# mp3player_v7_Laderegler_LTC4063_4050.net
KiCad netlist of a schematic drawn in EAGLE
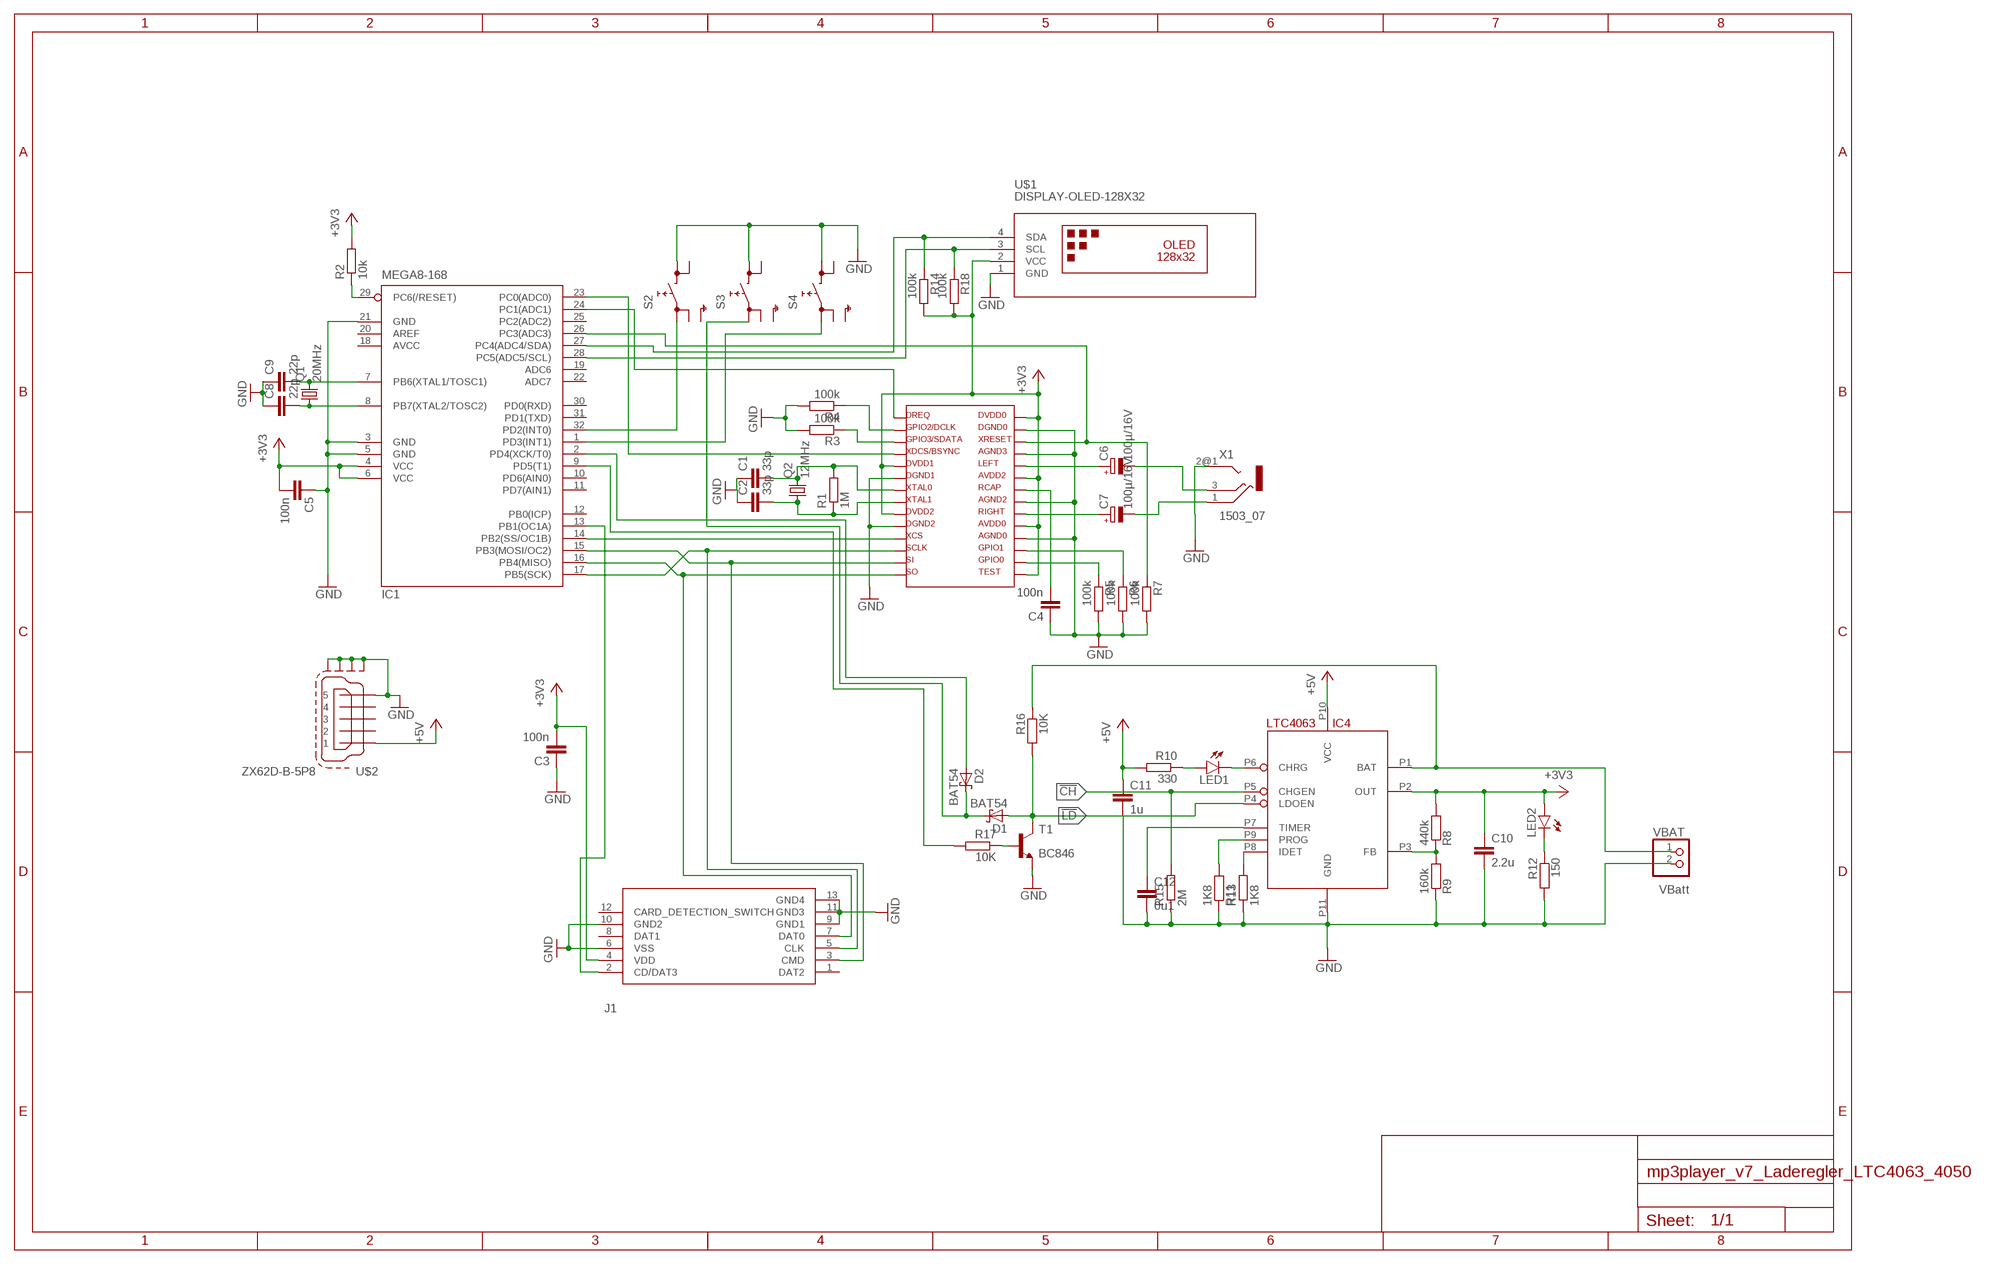
[diagram p0: schematic, sheet 1]

(export (version "E")
  (design (tool "Eeschema 10.0.6"))
  (components
    (comp (ref "C1")
      (value "33p")
      (footprint "eagle-import:C1206K")
      (libsource (lib "eagle-import") (part "C-EUC1206K"))
    )
    (comp (ref "C2")
      (value "33p")
      (footprint "eagle-import:C1206K")
      (libsource (lib "eagle-import") (part "C-EUC1206K"))
    )
    (comp (ref "C3")
      (value "100n")
      (footprint "eagle-import:C1206K")
      (libsource (lib "eagle-import") (part "C-EUC1206K"))
    )
    (comp (ref "C4")
      (value "100n")
      (footprint "eagle-import:C1206K")
      (libsource (lib "eagle-import") (part "C-EUC1206K"))
    )
    (comp (ref "C5")
      (value "100n")
      (footprint "eagle-import:C1206K")
      (libsource (lib "eagle-import") (part "C-EUC1206K"))
    )
    (comp (ref "C6")
      (value "100µ/16V")
      (footprint "eagle-import:UD-6,3X7,7_NICHICON")
      (libsource (lib "eagle-import") (part "CPOL-EUUD-6,3X7,7"))
    )
    (comp (ref "C7")
      (value "100µ/16V")
      (footprint "eagle-import:UD-6,3X7,7_NICHICON")
      (libsource (lib "eagle-import") (part "CPOL-EUUD-6,3X7,7"))
    )
    (comp (ref "C8")
      (value "22p")
      (footprint "eagle-import:C1206K")
      (libsource (lib "eagle-import") (part "rcl_334_C-EUC1206K"))
    )
    (comp (ref "C9")
      (value "22p")
      (footprint "eagle-import:C1206K")
      (libsource (lib "eagle-import") (part "rcl_334_C-EUC1206K"))
    )
    (comp (ref "C10")
      (value "2.2u")
      (footprint "eagle-import:C0805K")
      (libsource (lib "eagle-import") (part "C-EUC0805K"))
    )
    (comp (ref "C11")
      (value "1u")
      (footprint "eagle-import:C0805K")
      (libsource (lib "eagle-import") (part "C-EUC0805K"))
    )
    (comp (ref "C12")
      (value "0u1")
      (footprint "eagle-import:C0805K")
      (libsource (lib "eagle-import") (part "C-EUC0805K"))
    )
    (comp (ref "D1")
      (value "BAT54")
      (footprint "eagle-import:SOT23")
      (libsource (lib "eagle-import") (part "BAT54"))
    )
    (comp (ref "D2")
      (value "BAT54")
      (footprint "eagle-import:SOT23")
      (libsource (lib "eagle-import") (part "BAT54"))
    )
    (comp (ref "IC1")
      (value "MEGA8-168")
      (footprint "eagle-import:TQFP32-08")
      (fields (field (name "MPN") "ATMEGA8-16AU"))
      (libsource (lib "eagle-import") (part "MEGA8-AI"))
    )
    (comp (ref "IC2")
      (value "VS1011")
      (footprint "eagle-import:SOIC-28")
      (libsource (lib "eagle-import") (part "VS1011"))
    )
    (comp (ref "IC4")
      (value "LTC4063")
      (footprint "eagle-import:LTC4063")
      (libsource (lib "eagle-import") (part "LTC4063"))
    )
    (comp (ref "J1")
      (value "DM3CS-SF")
      (footprint "eagle-import:DM3CS-SF")
      (fields (field (name "RS_PART_NUMBER") "1664833"))
      (libsource (lib "eagle-import") (part "DM3CS-SF"))
    )
    (comp (ref "LED1")
      (value "LG_T679-E1F1-1")
      (footprint "eagle-import:PLCC2")
      (libsource (lib "eagle-import") (part "_T679-?-1E1F1LG"))
    )
    (comp (ref "LED2")
      (value "LG_T679-E1F1-1")
      (footprint "eagle-import:PLCC2")
      (libsource (lib "eagle-import") (part "_T679-?-1E1F1LG"))
    )
    (comp (ref "Q1")
      (value "20MHz")
      (footprint "eagle-import:HC49UP")
      (libsource (lib "eagle-import") (part "crystal_204_CRYSTALHC49UP"))
    )
    (comp (ref "Q2")
      (value "12MHz")
      (footprint "eagle-import:HC49UP")
      (libsource (lib "eagle-import") (part "CRYSTALHC49UP"))
    )
    (comp (ref "R1")
      (value "1M")
      (footprint "eagle-import:R0805")
      (libsource (lib "eagle-import") (part "rcl_334_R-EU_R0805"))
    )
    (comp (ref "R2")
      (value "10k")
      (footprint "eagle-import:0207_7")
      (libsource (lib "eagle-import") (part "rcl_334_R-EU_0207/7"))
    )
    (comp (ref "R3")
      (value "100k")
      (footprint "eagle-import:R0805")
      (libsource (lib "eagle-import") (part "rcl_334_R-EU_R0805"))
    )
    (comp (ref "R4")
      (value "100k")
      (footprint "eagle-import:R0805")
      (libsource (lib "eagle-import") (part "rcl_334_R-EU_R0805"))
    )
    (comp (ref "R5")
      (value "100k")
      (footprint "eagle-import:R0805")
      (libsource (lib "eagle-import") (part "rcl_334_R-EU_R0805"))
    )
    (comp (ref "R6")
      (value "100k")
      (footprint "eagle-import:R0805")
      (libsource (lib "eagle-import") (part "rcl_334_R-EU_R0805"))
    )
    (comp (ref "R7")
      (value "100k")
      (footprint "eagle-import:0207_15")
      (libsource (lib "eagle-import") (part "rcl_334_R-EU_0207/15"))
    )
    (comp (ref "R8")
      (value "440k")
      (footprint "eagle-import:R0805")
      (libsource (lib "eagle-import") (part "rcl_334_R-EU_R0805"))
    )
    (comp (ref "R9")
      (value "160k")
      (footprint "eagle-import:R0805")
      (libsource (lib "eagle-import") (part "rcl_334_R-EU_R0805"))
    )
    (comp (ref "R10")
      (value "330")
      (footprint "eagle-import:R0805")
      (libsource (lib "eagle-import") (part "rcl_334_R-EU_R0805"))
    )
    (comp (ref "R11")
      (value "1K8")
      (footprint "eagle-import:R0805")
      (libsource (lib "eagle-import") (part "R-EU_R0805"))
    )
    (comp (ref "R12")
      (value "150")
      (footprint "eagle-import:R0805")
      (libsource (lib "eagle-import") (part "rcl_334_R-EU_R0805"))
    )
    (comp (ref "R13")
      (value "1K8")
      (footprint "eagle-import:R0805")
      (libsource (lib "eagle-import") (part "rcl_334_R-EU_R0805"))
    )
    (comp (ref "R14")
      (value "100k")
      (footprint "eagle-import:R0805")
      (libsource (lib "eagle-import") (part "rcl_334_R-EU_R0805"))
    )
    (comp (ref "R15")
      (value "2M")
      (footprint "eagle-import:R0805")
      (libsource (lib "eagle-import") (part "rcl_334_R-EU_R0805"))
    )
    (comp (ref "R16")
      (value "10K")
      (footprint "eagle-import:0207_7")
      (libsource (lib "eagle-import") (part "rcl_334_R-EU_0207/7"))
    )
    (comp (ref "R17")
      (value "10K")
      (footprint "eagle-import:R0805")
      (libsource (lib "eagle-import") (part "rcl_334_R-EU_R0805"))
    )
    (comp (ref "R18")
      (value "100k")
      (footprint "eagle-import:R0805")
      (libsource (lib "eagle-import") (part "rcl_334_R-EU_R0805"))
    )
    (comp (ref "S2")
      (value "SKHMPSE010")
      (footprint "eagle-import:SKHMPXE010")
      (libsource (lib "eagle-import") (part "SKHMPE010S"))
    )
    (comp (ref "S3")
      (value "SKHMPSE010")
      (footprint "eagle-import:SKHMPXE010")
      (libsource (lib "eagle-import") (part "SKHMPE010S"))
    )
    (comp (ref "S4")
      (value "SKHMPSE010")
      (footprint "eagle-import:SKHMPXE010")
      (libsource (lib "eagle-import") (part "SKHMPE010S"))
    )
    (comp (ref "T1")
      (value "BC846")
      (footprint "eagle-import:SOT23")
      (libsource (lib "eagle-import") (part "BC846"))
    )
    (comp (ref "U$1")
      (value "DISPLAY-OLED-128X32")
      (footprint "eagle-import:DISPLAY-OLED-128X32")
      (libsource (lib "eagle-import") (part "DISPLAY-OLED-128X32"))
    )
    (comp (ref "U$2")
      (value "ZX62D-B-5P8")
      (footprint "eagle-import:ZX62D-B-5P8")
      (libsource (lib "eagle-import") (part "ZX62D-B-5P8"))
    )
    (comp (ref "VBAT")
      (value "PINHD-1X2")
      (footprint "eagle-import:1X02")
      (libsource (lib "eagle-import") (part "PINHD-1X2"))
    )
    (comp (ref "X1")
      (value "1503_07")
      (footprint "eagle-import:1503_07")
      (libsource (lib "eagle-import") (part "1503_?07"))
    )
  )
  (nets
    (net (code "1") (name "+3V3") (class "Default")
      (node (ref "C10") (pin "1") (pinfunction "1_1") (pintype "passive"))
      (node (ref "C3") (pin "2") (pinfunction "2_2") (pintype "passive"))
      (node (ref "C5") (pin "2") (pinfunction "2_2") (pintype "passive"))
      (node (ref "IC1") (pin "4") (pinfunction "VCC_4") (pintype "power_in"))
      (node (ref "IC1") (pin "6") (pinfunction "VCC_6") (pintype "power_in"))
      (node (ref "IC2") (pin "15") (pinfunction "P$15_15") (pintype "bidirectional"))
      (node (ref "IC2") (pin "19") (pinfunction "P$19_19") (pintype "bidirectional"))
      (node (ref "IC2") (pin "23") (pinfunction "P$23_23") (pintype "bidirectional"))
      (node (ref "IC2") (pin "28") (pinfunction "P$28_28") (pintype "bidirectional"))
      (node (ref "IC2") (pin "5") (pinfunction "P$5_5") (pintype "bidirectional"))
      (node (ref "IC2") (pin "9") (pinfunction "P$9_9") (pintype "bidirectional"))
      (node (ref "IC4") (pin "P2") (pinfunction "OUT_P2") (pintype "output"))
      (node (ref "J1") (pin "4") (pinfunction "VDD_4") (pintype "bidirectional"))
      (node (ref "LED2") (pin "A") (pinfunction "A_A") (pintype "passive"))
      (node (ref "R14") (pin "2") (pinfunction "2_2") (pintype "passive"))
      (node (ref "R18") (pin "2") (pinfunction "2_2") (pintype "passive"))
      (node (ref "R2") (pin "2") (pinfunction "2_2") (pintype "passive"))
      (node (ref "R8") (pin "2") (pinfunction "2_2") (pintype "passive"))
      (node (ref "U$1") (pin "2") (pinfunction "VCC_2") (pintype "power_in"))
    )
    (net (code "2") (name "+5V") (class "Default")
      (node (ref "C11") (pin "1") (pinfunction "1_1") (pintype "passive"))
      (node (ref "IC4") (pin "P10") (pinfunction "VCC_P10") (pintype "power_in"))
      (node (ref "R10") (pin "2") (pinfunction "2_2") (pintype "passive"))
      (node (ref "U$2") (pin "P$1") (pinfunction "1_P$1") (pintype "passive"))
    )
    (net (code "3") (name "/AVCC") (class "Default")
      (node (ref "IC1") (pin "18") (pinfunction "AVCC_18") (pintype "power_in"))
    )
    (net (code "4") (name "/~{CH}") (class "Default")
      (node (ref "IC4") (pin "P5") (pinfunction "CHGEN_P5") (pintype "input"))
      (node (ref "R15") (pin "2") (pinfunction "2_2") (pintype "passive"))
    )
    (net (code "5") (name "/~{LD}") (class "Default")
      (node (ref "D1") (pin "1") (pinfunction "A_1") (pintype "passive"))
      (node (ref "IC4") (pin "P4") (pinfunction "LDOEN_P4") (pintype "input"))
      (node (ref "R16") (pin "2") (pinfunction "2_2") (pintype "passive"))
      (node (ref "T1") (pin "3") (pinfunction "C_3") (pintype "passive"))
    )
    (net (code "6") (name "GND") (class "Default")
      (node (ref "C1") (pin "1") (pinfunction "1_1") (pintype "passive"))
      (node (ref "C10") (pin "2") (pinfunction "2_2") (pintype "passive"))
      (node (ref "C11") (pin "2") (pinfunction "2_2") (pintype "passive"))
      (node (ref "C12") (pin "2") (pinfunction "2_2") (pintype "passive"))
      (node (ref "C2") (pin "1") (pinfunction "1_1") (pintype "passive"))
      (node (ref "C3") (pin "1") (pinfunction "1_1") (pintype "passive"))
      (node (ref "C4") (pin "1") (pinfunction "1_1") (pintype "passive"))
      (node (ref "C5") (pin "1") (pinfunction "1_1") (pintype "passive"))
      (node (ref "C8") (pin "1") (pinfunction "1_1") (pintype "passive"))
      (node (ref "C9") (pin "1") (pinfunction "1_1") (pintype "passive"))
      (node (ref "IC1") (pin "21") (pinfunction "GND_21") (pintype "power_in"))
      (node (ref "IC1") (pin "3") (pinfunction "GND_3") (pintype "power_in"))
      (node (ref "IC1") (pin "5") (pinfunction "GND_5") (pintype "power_in"))
      (node (ref "IC2") (pin "10") (pinfunction "P$10_10") (pintype "bidirectional"))
      (node (ref "IC2") (pin "18") (pinfunction "P$18_18") (pintype "bidirectional"))
      (node (ref "IC2") (pin "21") (pinfunction "P$21_21") (pintype "bidirectional"))
      (node (ref "IC2") (pin "25") (pinfunction "P$25_25") (pintype "bidirectional"))
      (node (ref "IC2") (pin "27") (pinfunction "P$27_27") (pintype "bidirectional"))
      (node (ref "IC2") (pin "6") (pinfunction "P$6_6") (pintype "bidirectional"))
      (node (ref "IC4") (pin "P11") (pinfunction "GND_P11") (pintype "power_in"))
      (node (ref "J1") (pin "10") (pinfunction "GND2_10") (pintype "bidirectional"))
      (node (ref "J1") (pin "11") (pinfunction "GND3_11") (pintype "bidirectional"))
      (node (ref "J1") (pin "13") (pinfunction "GND4_13") (pintype "bidirectional"))
      (node (ref "J1") (pin "6") (pinfunction "VSS_6") (pintype "bidirectional"))
      (node (ref "J1") (pin "9") (pinfunction "GND1_9") (pintype "bidirectional"))
      (node (ref "R11") (pin "1") (pinfunction "1_1") (pintype "passive"))
      (node (ref "R12") (pin "2") (pinfunction "2_2") (pintype "passive"))
      (node (ref "R13") (pin "1") (pinfunction "1_1") (pintype "passive"))
      (node (ref "R15") (pin "1") (pinfunction "1_1") (pintype "passive"))
      (node (ref "R3") (pin "2") (pinfunction "2_2") (pintype "passive"))
      (node (ref "R4") (pin "2") (pinfunction "2_2") (pintype "passive"))
      (node (ref "R5") (pin "2") (pinfunction "2_2") (pintype "passive"))
      (node (ref "R6") (pin "2") (pinfunction "2_2") (pintype "passive"))
      (node (ref "R7") (pin "2") (pinfunction "2_2") (pintype "passive"))
      (node (ref "R9") (pin "1") (pinfunction "1_1") (pintype "passive"))
      (node (ref "S2") (pin "3") (pinfunction "2.1_3") (pintype "passive"))
      (node (ref "S3") (pin "3") (pinfunction "2.1_3") (pintype "passive"))
      (node (ref "S4") (pin "3") (pinfunction "2.1_3") (pintype "passive"))
      (node (ref "T1") (pin "2") (pinfunction "E_2") (pintype "passive"))
      (node (ref "U$1") (pin "1") (pinfunction "GND_1") (pintype "power_in"))
      (node (ref "U$2") (pin "P$5") (pinfunction "5_P$5") (pintype "passive"))
      (node (ref "U$2") (pin "SH1") (pinfunction "SH1_SH1") (pintype "passive"))
      (node (ref "U$2") (pin "SH2") (pinfunction "SH2_SH2") (pintype "passive"))
      (node (ref "U$2") (pin "SH3") (pinfunction "SH3_SH3") (pintype "passive"))
      (node (ref "U$2") (pin "SH4") (pinfunction "SH4_SH4") (pintype "passive"))
      (node (ref "VBAT") (pin "2") (pinfunction "2_2") (pintype "passive"))
      (node (ref "X1") (pin "2@1") (pinfunction "2_2@1") (pintype "passive"))
    )
    (net (code "7") (name "Net-(C6-Pad-)") (class "Default")
      (node (ref "C6") (pin "-") (pinfunction "-_-") (pintype "passive"))
      (node (ref "X1") (pin "3") (pinfunction "3_3") (pintype "passive"))
    )
    (net (code "8") (name "Net-(C7-Pad-)") (class "Default")
      (node (ref "C7") (pin "-") (pinfunction "-_-") (pintype "passive"))
      (node (ref "X1") (pin "1") (pinfunction "1_1") (pintype "passive"))
    )
    (net (code "9") (name "Net-(D1-C)") (class "Default")
      (node (ref "D1") (pin "3") (pinfunction "C_3") (pintype "passive"))
      (node (ref "D2") (pin "3") (pinfunction "C_3") (pintype "passive"))
      (node (ref "S3") (pin "1") (pinfunction "1.1_1") (pintype "passive"))
    )
    (net (code "10") (name "Net-(D2-A)") (class "Default")
      (node (ref "D2") (pin "1") (pinfunction "A_1") (pintype "passive"))
      (node (ref "IC1") (pin "2") (pinfunction "PD4(XCK/T0)_2") (pintype "bidirectional"))
    )
    (net (code "11") (name "Net-(IC1-PB1(OC1A))") (class "Default")
      (node (ref "IC1") (pin "13") (pinfunction "PB1(OC1A)_13") (pintype "bidirectional"))
      (node (ref "J1") (pin "2") (pinfunction "CD/DAT3_2") (pintype "bidirectional"))
    )
    (net (code "12") (name "Net-(IC1-PB2(SS{slash}OC1B))") (class "Default")
      (node (ref "IC1") (pin "14") (pinfunction "PB2(SS/OC1B)_14") (pintype "bidirectional"))
      (node (ref "IC2") (pin "11") (pinfunction "P$11_11") (pintype "bidirectional"))
    )
    (net (code "13") (name "Net-(IC1-PB3(MOSI{slash}OC2))") (class "Default")
      (node (ref "IC1") (pin "15") (pinfunction "PB3(MOSI/OC2)_15") (pintype "bidirectional"))
      (node (ref "IC2") (pin "13") (pinfunction "P$13_13") (pintype "bidirectional"))
      (node (ref "J1") (pin "3") (pinfunction "CMD_3") (pintype "bidirectional"))
    )
    (net (code "14") (name "Net-(IC1-PB4(MISO))") (class "Default")
      (node (ref "IC1") (pin "16") (pinfunction "PB4(MISO)_16") (pintype "bidirectional"))
      (node (ref "IC2") (pin "14") (pinfunction "P$14_14") (pintype "bidirectional"))
      (node (ref "J1") (pin "7") (pinfunction "DAT0_7") (pintype "bidirectional"))
    )
    (net (code "15") (name "Net-(IC1-PB5(SCK))") (class "Default")
      (node (ref "IC1") (pin "17") (pinfunction "PB5(SCK)_17") (pintype "bidirectional"))
      (node (ref "IC2") (pin "12") (pinfunction "P$12_12") (pintype "bidirectional"))
      (node (ref "J1") (pin "5") (pinfunction "CLK_5") (pintype "bidirectional"))
    )
    (net (code "16") (name "Net-(IC1-PB6(XTAL1{slash}TOSC1))") (class "Default")
      (node (ref "C9") (pin "2") (pinfunction "2_2") (pintype "passive"))
      (node (ref "IC1") (pin "7") (pinfunction "PB6(XTAL1/TOSC1)_7") (pintype "bidirectional"))
      (node (ref "Q1") (pin "2") (pinfunction "2_2") (pintype "passive"))
    )
    (net (code "17") (name "Net-(IC1-PB7(XTAL2{slash}TOSC2))") (class "Default")
      (node (ref "C8") (pin "2") (pinfunction "2_2") (pintype "passive"))
      (node (ref "IC1") (pin "8") (pinfunction "PB7(XTAL2/TOSC2)_8") (pintype "bidirectional"))
      (node (ref "Q1") (pin "1") (pinfunction "1_1") (pintype "passive"))
    )
    (net (code "18") (name "Net-(IC1-PC0(ADC0))") (class "Default")
      (node (ref "IC1") (pin "23") (pinfunction "PC0(ADC0)_23") (pintype "bidirectional"))
      (node (ref "IC2") (pin "4") (pinfunction "P$4_4") (pintype "bidirectional"))
    )
    (net (code "19") (name "Net-(IC1-PC1(ADC1))") (class "Default")
      (node (ref "IC1") (pin "24") (pinfunction "PC1(ADC1)_24") (pintype "bidirectional"))
      (node (ref "IC2") (pin "1") (pinfunction "P$1_1") (pintype "bidirectional"))
    )
    (net (code "20") (name "Net-(IC1-PC3(ADC3))") (class "Default")
      (node (ref "IC1") (pin "26") (pinfunction "PC3(ADC3)_26") (pintype "bidirectional"))
      (node (ref "IC2") (pin "26") (pinfunction "P$26_26") (pintype "bidirectional"))
      (node (ref "R7") (pin "1") (pinfunction "1_1") (pintype "passive"))
    )
    (net (code "21") (name "Net-(IC1-PC4(ADC4{slash}SDA))") (class "Default")
      (node (ref "IC1") (pin "27") (pinfunction "PC4(ADC4/SDA)_27") (pintype "bidirectional"))
      (node (ref "R14") (pin "1") (pinfunction "1_1") (pintype "passive"))
      (node (ref "U$1") (pin "4") (pinfunction "SDA_4") (pintype "bidirectional"))
    )
    (net (code "22") (name "Net-(IC1-PC5(ADC5{slash}SCL))") (class "Default")
      (node (ref "IC1") (pin "28") (pinfunction "PC5(ADC5/SCL)_28") (pintype "bidirectional"))
      (node (ref "R18") (pin "1") (pinfunction "1_1") (pintype "passive"))
      (node (ref "U$1") (pin "3") (pinfunction "SCL_3") (pintype "bidirectional"))
    )
    (net (code "23") (name "Net-(IC1-PC6({slash}RESET))") (class "Default")
      (node (ref "IC1") (pin "29") (pinfunction "PC6(/RESET)_29") (pintype "bidirectional"))
      (node (ref "R2") (pin "1") (pinfunction "1_1") (pintype "passive"))
    )
    (net (code "24") (name "Net-(IC1-PD2(INT0))") (class "Default")
      (node (ref "IC1") (pin "32") (pinfunction "PD2(INT0)_32") (pintype "bidirectional"))
      (node (ref "S2") (pin "1") (pinfunction "1.1_1") (pintype "passive"))
    )
    (net (code "25") (name "Net-(IC1-PD3(INT1))") (class "Default")
      (node (ref "IC1") (pin "1") (pinfunction "PD3(INT1)_1") (pintype "bidirectional"))
      (node (ref "S4") (pin "1") (pinfunction "1.1_1") (pintype "passive"))
    )
    (net (code "26") (name "Net-(IC1-PD5(T1))") (class "Default")
      (node (ref "IC1") (pin "9") (pinfunction "PD5(T1)_9") (pintype "bidirectional"))
      (node (ref "R17") (pin "2") (pinfunction "2_2") (pintype "passive"))
    )
    (net (code "27") (name "Net-(IC2-P$2)") (class "Default")
      (node (ref "IC2") (pin "2") (pinfunction "P$2_2") (pintype "bidirectional"))
      (node (ref "R4") (pin "1") (pinfunction "1_1") (pintype "passive"))
    )
    (net (code "28") (name "Net-(IC2-P$3)") (class "Default")
      (node (ref "IC2") (pin "3") (pinfunction "P$3_3") (pintype "bidirectional"))
      (node (ref "R3") (pin "1") (pinfunction "1_1") (pintype "passive"))
    )
    (net (code "29") (name "Net-(IC2-P$7)") (class "Default")
      (node (ref "C1") (pin "2") (pinfunction "2_2") (pintype "passive"))
      (node (ref "IC2") (pin "7") (pinfunction "P$7_7") (pintype "bidirectional"))
      (node (ref "Q2") (pin "2") (pinfunction "2_2") (pintype "passive"))
      (node (ref "R1") (pin "2") (pinfunction "2_2") (pintype "passive"))
    )
    (net (code "30") (name "Net-(IC2-P$8)") (class "Default")
      (node (ref "C2") (pin "2") (pinfunction "2_2") (pintype "passive"))
      (node (ref "IC2") (pin "8") (pinfunction "P$8_8") (pintype "bidirectional"))
      (node (ref "Q2") (pin "1") (pinfunction "1_1") (pintype "passive"))
      (node (ref "R1") (pin "1") (pinfunction "1_1") (pintype "passive"))
    )
    (net (code "31") (name "Net-(IC2-P$16)") (class "Default")
      (node (ref "IC2") (pin "16") (pinfunction "P$16_16") (pintype "bidirectional"))
      (node (ref "R5") (pin "1") (pinfunction "1_1") (pintype "passive"))
    )
    (net (code "32") (name "Net-(IC2-P$17)") (class "Default")
      (node (ref "IC2") (pin "17") (pinfunction "P$17_17") (pintype "bidirectional"))
      (node (ref "R6") (pin "1") (pinfunction "1_1") (pintype "passive"))
    )
    (net (code "33") (name "Net-(IC2-P$20)") (class "Default")
      (node (ref "C7") (pin "+") (pinfunction "+_+") (pintype "passive"))
      (node (ref "IC2") (pin "20") (pinfunction "P$20_20") (pintype "bidirectional"))
    )
    (net (code "34") (name "Net-(IC2-P$22)") (class "Default")
      (node (ref "C4") (pin "2") (pinfunction "2_2") (pintype "passive"))
      (node (ref "IC2") (pin "22") (pinfunction "P$22_22") (pintype "bidirectional"))
    )
    (net (code "35") (name "Net-(IC2-P$24)") (class "Default")
      (node (ref "C6") (pin "+") (pinfunction "+_+") (pintype "passive"))
      (node (ref "IC2") (pin "24") (pinfunction "P$24_24") (pintype "bidirectional"))
    )
    (net (code "36") (name "Net-(IC4-BAT)") (class "Default")
      (node (ref "IC4") (pin "P1") (pinfunction "BAT_P1") (pintype "output"))
      (node (ref "R16") (pin "1") (pinfunction "1_1") (pintype "passive"))
      (node (ref "VBAT") (pin "1") (pinfunction "1_1") (pintype "passive"))
    )
    (net (code "37") (name "Net-(IC4-CHRG)") (class "Default")
      (node (ref "IC4") (pin "P6") (pinfunction "CHRG_P6") (pintype "output"))
      (node (ref "LED1") (pin "C") (pinfunction "C_C") (pintype "passive"))
    )
    (net (code "38") (name "Net-(IC4-FB)") (class "Default")
      (node (ref "IC4") (pin "P3") (pinfunction "FB_P3") (pintype "passive"))
      (node (ref "R8") (pin "1") (pinfunction "1_1") (pintype "passive"))
      (node (ref "R9") (pin "2") (pinfunction "2_2") (pintype "passive"))
    )
    (net (code "39") (name "Net-(IC4-IDET)") (class "Default")
      (node (ref "IC4") (pin "P8") (pinfunction "IDET_P8") (pintype "passive"))
      (node (ref "R13") (pin "2") (pinfunction "2_2") (pintype "passive"))
    )
    (net (code "40") (name "Net-(IC4-PROG)") (class "Default")
      (node (ref "IC4") (pin "P9") (pinfunction "PROG_P9") (pintype "passive"))
      (node (ref "R11") (pin "2") (pinfunction "2_2") (pintype "passive"))
    )
    (net (code "41") (name "Net-(IC4-TIMER)") (class "Default")
      (node (ref "C12") (pin "1") (pinfunction "1_1") (pintype "passive"))
      (node (ref "IC4") (pin "P7") (pinfunction "TIMER_P7") (pintype "passive"))
    )
    (net (code "42") (name "Net-(LED1-PadA)") (class "Default")
      (node (ref "LED1") (pin "A") (pinfunction "A_A") (pintype "passive"))
      (node (ref "R10") (pin "1") (pinfunction "1_1") (pintype "passive"))
    )
    (net (code "43") (name "Net-(LED2-PadC)") (class "Default")
      (node (ref "LED2") (pin "C") (pinfunction "C_C") (pintype "passive"))
      (node (ref "R12") (pin "1") (pinfunction "1_1") (pintype "passive"))
    )
    (net (code "44") (name "Net-(T1-B)") (class "Default")
      (node (ref "R17") (pin "1") (pinfunction "1_1") (pintype "passive"))
      (node (ref "T1") (pin "1") (pinfunction "B_1") (pintype "passive"))
    )
    (net (code "45") (name "unconnected-(IC1-ADC6-Pad19)") (class "Default")
      (node (ref "IC1") (pin "19") (pinfunction "ADC6_19") (pintype "bidirectional"))
    )
    (net (code "46") (name "unconnected-(IC1-ADC7-Pad22)") (class "Default")
      (node (ref "IC1") (pin "22") (pinfunction "ADC7_22") (pintype "bidirectional"))
    )
    (net (code "47") (name "unconnected-(IC1-AREF-Pad20)") (class "Default")
      (node (ref "IC1") (pin "20") (pinfunction "AREF_20") (pintype "passive"))
    )
    (net (code "48") (name "unconnected-(IC1-PB0(ICP)-Pad12)") (class "Default")
      (node (ref "IC1") (pin "12") (pinfunction "PB0(ICP)_12") (pintype "bidirectional"))
    )
    (net (code "49") (name "unconnected-(IC1-PC2(ADC2)-Pad25)") (class "Default")
      (node (ref "IC1") (pin "25") (pinfunction "PC2(ADC2)_25") (pintype "bidirectional"))
    )
    (net (code "50") (name "unconnected-(IC1-PD0(RXD)-Pad30)") (class "Default")
      (node (ref "IC1") (pin "30") (pinfunction "PD0(RXD)_30") (pintype "bidirectional"))
    )
    (net (code "51") (name "unconnected-(IC1-PD1(TXD)-Pad31)") (class "Default")
      (node (ref "IC1") (pin "31") (pinfunction "PD1(TXD)_31") (pintype "bidirectional"))
    )
    (net (code "52") (name "unconnected-(IC1-PD6(AIN0)-Pad10)") (class "Default")
      (node (ref "IC1") (pin "10") (pinfunction "PD6(AIN0)_10") (pintype "bidirectional"))
    )
    (net (code "53") (name "unconnected-(IC1-PD7(AIN1)-Pad11)") (class "Default")
      (node (ref "IC1") (pin "11") (pinfunction "PD7(AIN1)_11") (pintype "bidirectional"))
    )
    (net (code "54") (name "unconnected-(J1-CARD_DETECTION_SWITCH-Pad12)") (class "Default")
      (node (ref "J1") (pin "12") (pinfunction "CARD_DETECTION_SWITCH_12") (pintype "bidirectional"))
    )
    (net (code "55") (name "unconnected-(J1-DAT1-Pad8)") (class "Default")
      (node (ref "J1") (pin "8") (pinfunction "DAT1_8") (pintype "bidirectional"))
    )
    (net (code "56") (name "unconnected-(J1-DAT2-Pad1)") (class "Default")
      (node (ref "J1") (pin "1") (pinfunction "DAT2_1") (pintype "bidirectional"))
    )
    (net (code "57") (name "unconnected-(S2-1.2-Pad2)") (class "Default")
      (node (ref "S2") (pin "2") (pinfunction "1.2_2") (pintype "passive"))
    )
    (net (code "58") (name "unconnected-(S2-2.2-Pad4)") (class "Default")
      (node (ref "S2") (pin "4") (pinfunction "2.2_4") (pintype "passive"))
    )
    (net (code "59") (name "unconnected-(S2-SH-Pad5)") (class "Default")
      (node (ref "S2") (pin "5") (pinfunction "SH_5") (pintype "passive"))
    )
    (net (code "60") (name "unconnected-(S3-1.2-Pad2)") (class "Default")
      (node (ref "S3") (pin "2") (pinfunction "1.2_2") (pintype "passive"))
    )
    (net (code "61") (name "unconnected-(S3-2.2-Pad4)") (class "Default")
      (node (ref "S3") (pin "4") (pinfunction "2.2_4") (pintype "passive"))
    )
    (net (code "62") (name "unconnected-(S3-SH-Pad5)") (class "Default")
      (node (ref "S3") (pin "5") (pinfunction "SH_5") (pintype "passive"))
    )
    (net (code "63") (name "unconnected-(S4-1.2-Pad2)") (class "Default")
      (node (ref "S4") (pin "2") (pinfunction "1.2_2") (pintype "passive"))
    )
    (net (code "64") (name "unconnected-(S4-2.2-Pad4)") (class "Default")
      (node (ref "S4") (pin "4") (pinfunction "2.2_4") (pintype "passive"))
    )
    (net (code "65") (name "unconnected-(S4-SH-Pad5)") (class "Default")
      (node (ref "S4") (pin "5") (pinfunction "SH_5") (pintype "passive"))
    )
    (net (code "66") (name "unconnected-(U$2-2-PadP$2)") (class "Default")
      (node (ref "U$2") (pin "P$2") (pinfunction "2_P$2") (pintype "passive"))
    )
    (net (code "67") (name "unconnected-(U$2-3-PadP$3)") (class "Default")
      (node (ref "U$2") (pin "P$3") (pinfunction "3_P$3") (pintype "passive"))
    )
    (net (code "68") (name "unconnected-(U$2-4-PadP$4)") (class "Default")
      (node (ref "U$2") (pin "P$4") (pinfunction "4_P$4") (pintype "passive"))
    )
    (net (code "69") (name "unconnected-(X1-2-Pad2@2)") (class "Default")
      (node (ref "X1") (pin "2@2") (pinfunction "2_2@2") (pintype "passive"))
    )
  )
)
